# SCH_arduino_2021-11-24.net
KiCad netlist of a schematic drawn in EasyEDA
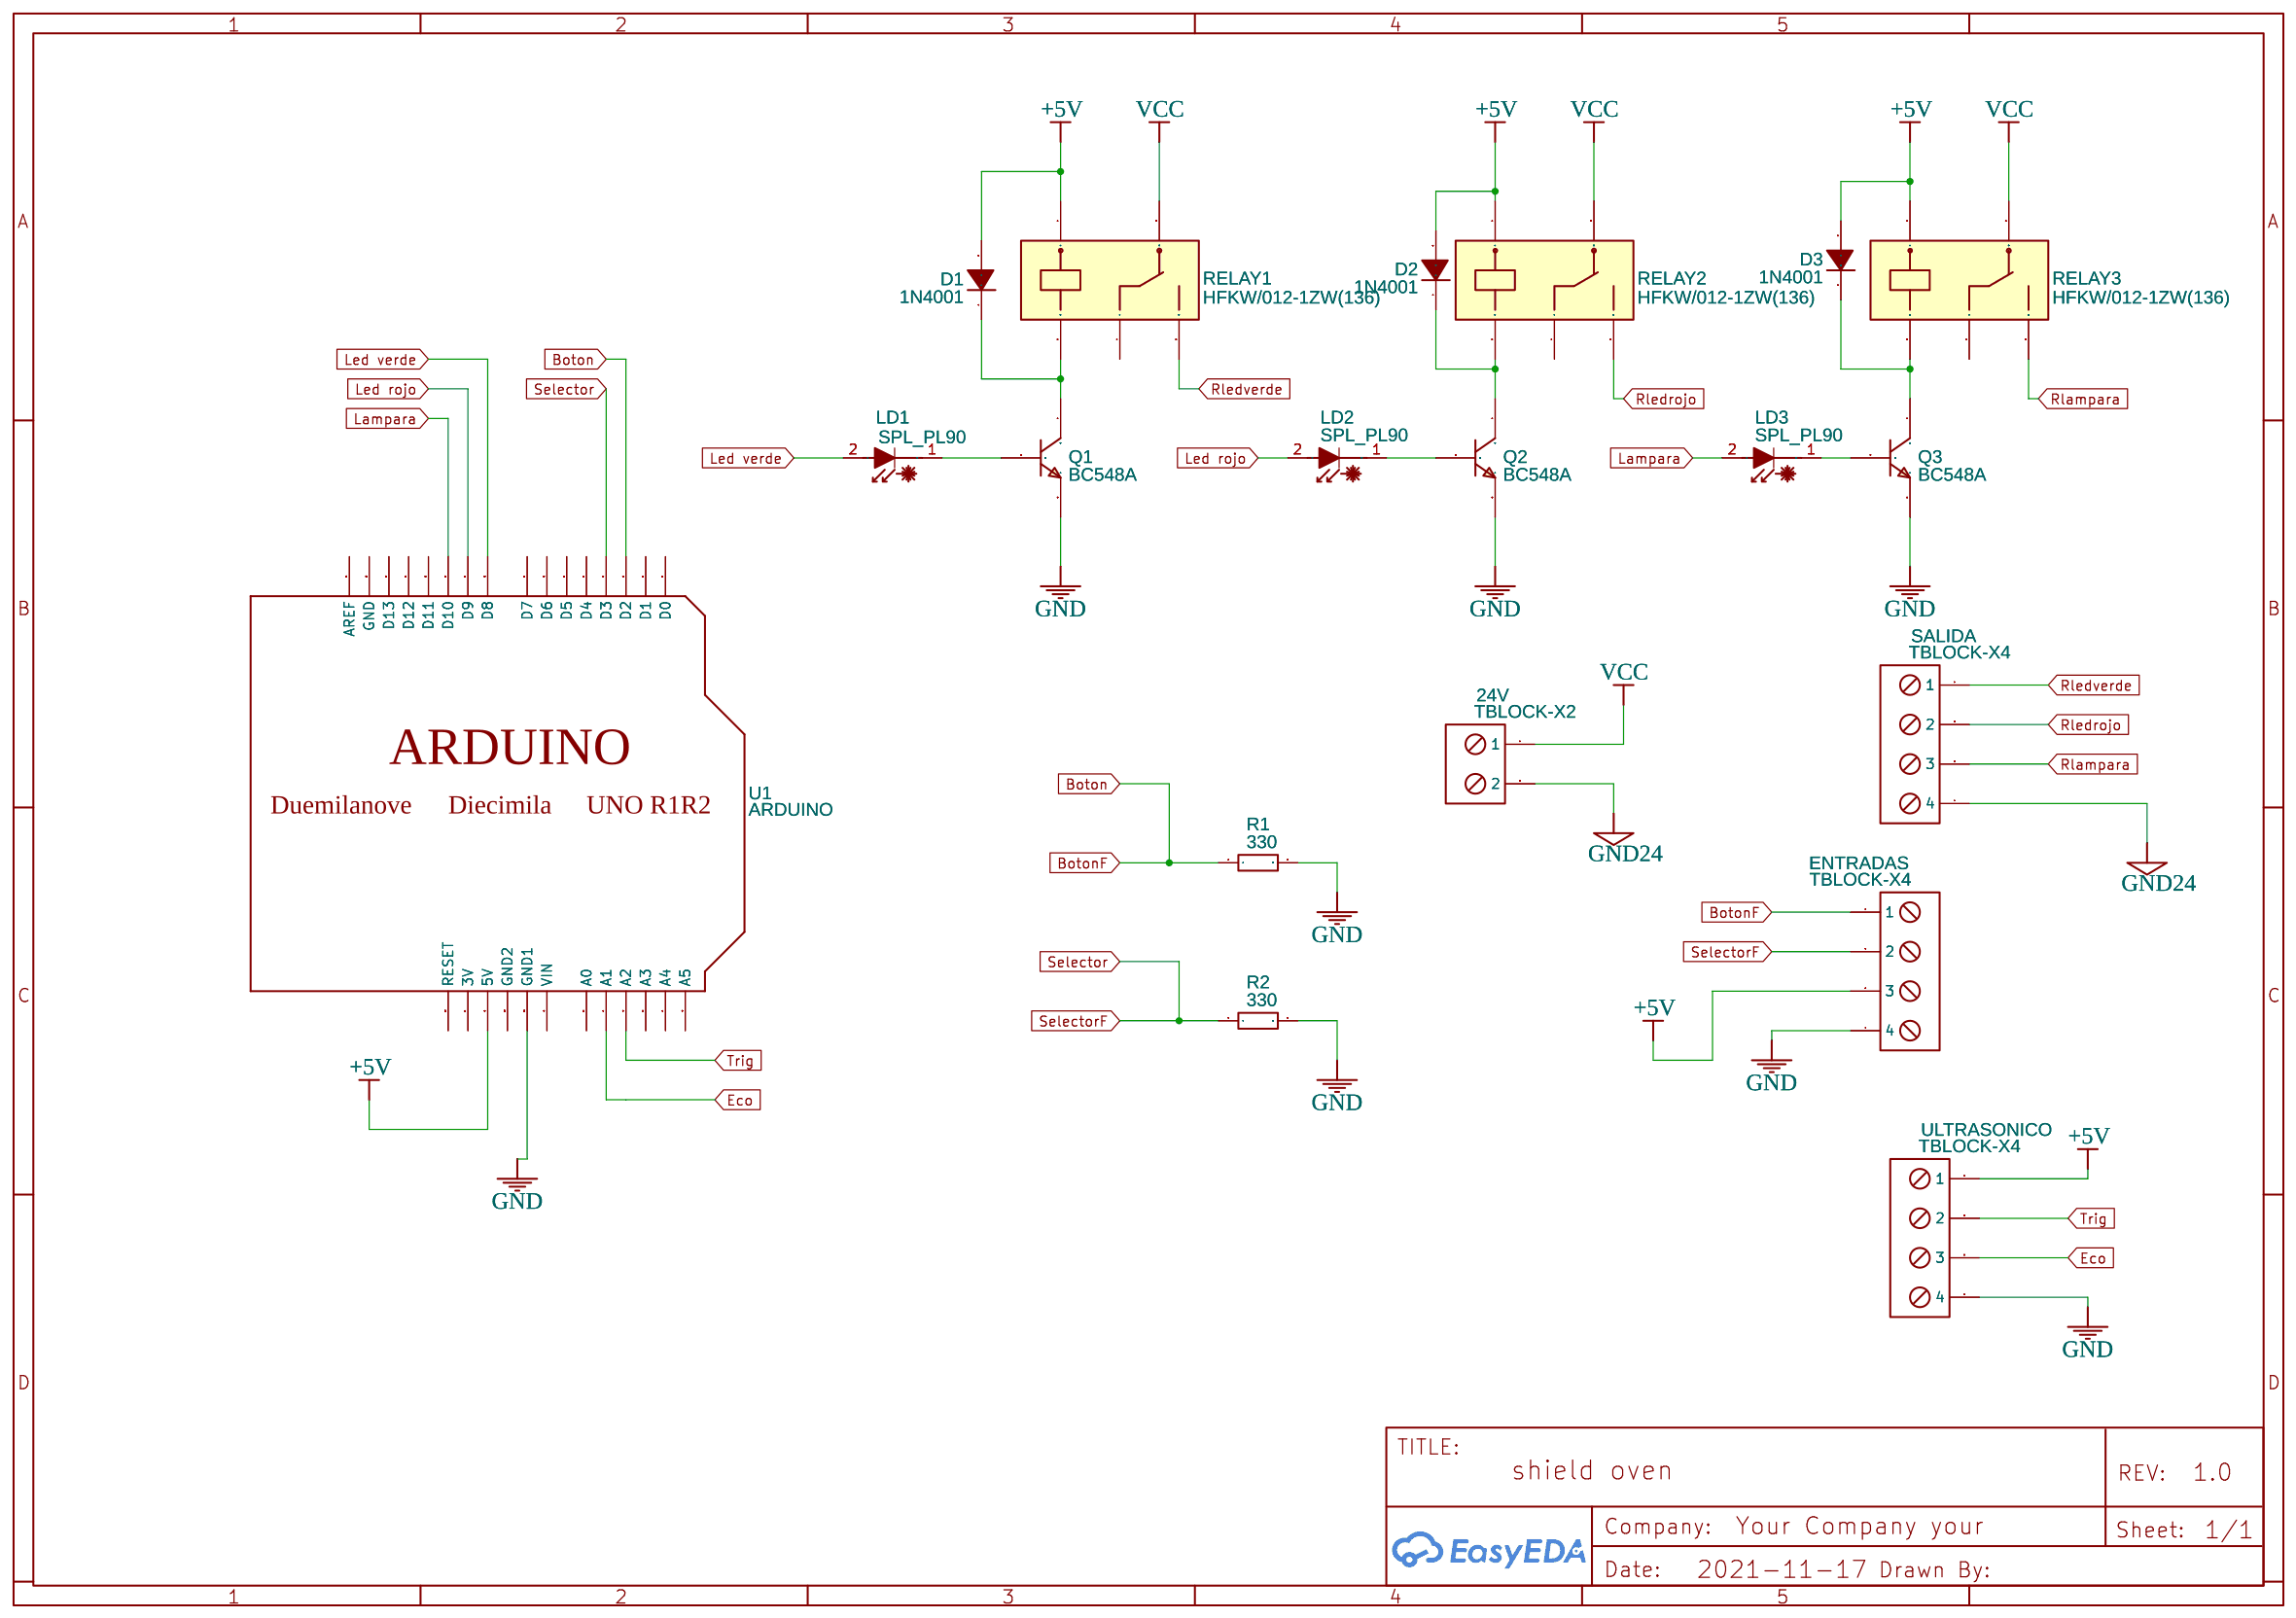
[diagram p0: schematic sheet]

(export (version "E")
  (design (tool "Eeschema 10.0.6"))
  (components
    (comp (ref "24V") (value "TBLOCK-X2") (libsource (lib "") (part "TBLOCK-X2")))
    (comp (ref "D1")
      (value "1N4001")
      (fields (field (name "BOM_Supplier Part") "C82804"))
      (libsource (lib "") (part "1N4001"))
    )
    (comp (ref "D2")
      (value "1N4001")
      (fields (field (name "BOM_Supplier Part") "C82804"))
      (libsource (lib "") (part "1N4001"))
    )
    (comp (ref "D3")
      (value "1N4001")
      (fields (field (name "BOM_Supplier Part") "C82804"))
      (libsource (lib "") (part "1N4001"))
    )
    (comp (ref "ENTRADAS") (value "TBLOCK-X4") (libsource (lib "") (part "TBLOCK-X4_2")))
    (comp (ref "LD1") (value "SPL_PL90") (libsource (lib "") (part "SPL_PL90")))
    (comp (ref "LD2") (value "SPL_PL90") (libsource (lib "") (part "SPL_PL90")))
    (comp (ref "LD3") (value "SPL_PL90") (libsource (lib "") (part "SPL_PL90")))
    (comp (ref "Q1") (value "BC548A") (libsource (lib "") (part "BC548A")))
    (comp (ref "Q2") (value "BC548A") (libsource (lib "") (part "BC548A")))
    (comp (ref "Q3") (value "BC548A") (libsource (lib "") (part "BC548A")))
    (comp (ref "R1")
      (value "330")
      (fields (field (name "BOM_Supplier Part") "C10322"))
      (libsource (lib "") (part "330Ω (331) ±5%"))
    )
    (comp (ref "R2")
      (value "330")
      (fields (field (name "BOM_Supplier Part") "C10322"))
      (libsource (lib "") (part "330Ω (331) ±5%"))
    )
    (comp (ref "RELAY1") (value "HFKW/012-1ZW(136)") (libsource (lib "") (part "HFKW/012-1ZW(136)")))
    (comp (ref "RELAY2") (value "HFKW/012-1ZW(136)") (libsource (lib "") (part "HFKW/012-1ZW(136)")))
    (comp (ref "RELAY3") (value "HFKW/012-1ZW(136)") (libsource (lib "") (part "HFKW/012-1ZW(136)")))
    (comp (ref "SALIDA") (value "TBLOCK-X4") (libsource (lib "") (part "TBLOCK-X4")))
    (comp (ref "U1") (value "ARDUINO") (libsource (lib "") (part "ARDUINO")))
    (comp (ref "ULTRASONICO") (value "TBLOCK-X4") (libsource (lib "") (part "TBLOCK-X4_1")))
  )
  (nets
    (net (code "1") (name "+5V") (class "Default")
      (node (ref "D1") (pin "2") (pinfunction "A_2") (pintype "unspecified"))
      (node (ref "D2") (pin "2") (pinfunction "A_2") (pintype "unspecified"))
      (node (ref "D3") (pin "2") (pinfunction "A_2") (pintype "unspecified"))
      (node (ref "ENTRADAS") (pin "3") (pinfunction "3_3") (pintype "unspecified"))
      (node (ref "RELAY1") (pin "1") (pinfunction "1_1") (pintype "input"))
      (node (ref "RELAY2") (pin "1") (pinfunction "1_1") (pintype "input"))
      (node (ref "RELAY3") (pin "1") (pinfunction "1_1") (pintype "input"))
      (node (ref "U1") (pin "5V") (pinfunction "5V_5V") (pintype "passive"))
      (node (ref "ULTRASONICO") (pin "1") (pinfunction "1_1") (pintype "unspecified"))
    )
    (net (code "2") (name "Boton") (class "Default")
      (node (ref "ENTRADAS") (pin "1") (pinfunction "1_1") (pintype "unspecified"))
      (node (ref "R1") (pin "1") (pinfunction "1_1") (pintype "unspecified"))
      (node (ref "U1") (pin "D2") (pinfunction "D2_D2") (pintype "unspecified"))
    )
    (net (code "3") (name "Eco") (class "Default")
      (node (ref "U1") (pin "A1") (pinfunction "A1_A1") (pintype "unspecified"))
      (node (ref "ULTRASONICO") (pin "3") (pinfunction "3_3") (pintype "unspecified"))
    )
    (net (code "4") (name "GND") (class "Default")
      (node (ref "ENTRADAS") (pin "4") (pinfunction "4_4") (pintype "unspecified"))
      (node (ref "Q1") (pin "3") (pinfunction "E_3") (pintype "unspecified"))
      (node (ref "Q2") (pin "3") (pinfunction "E_3") (pintype "unspecified"))
      (node (ref "Q3") (pin "3") (pinfunction "E_3") (pintype "unspecified"))
      (node (ref "R1") (pin "2") (pinfunction "2_2") (pintype "unspecified"))
      (node (ref "R2") (pin "2") (pinfunction "2_2") (pintype "unspecified"))
      (node (ref "U1") (pin "GND1") (pinfunction "GND1_GND1") (pintype "passive"))
      (node (ref "ULTRASONICO") (pin "4") (pinfunction "4_4") (pintype "unspecified"))
    )
    (net (code "5") (name "GND24") (class "Default")
      (node (ref "24V") (pin "2") (pinfunction "2_2") (pintype "unspecified"))
      (node (ref "SALIDA") (pin "4") (pinfunction "4_4") (pintype "unspecified"))
    )
    (net (code "6") (name "Lampara") (class "Default")
      (node (ref "LD3") (pin "2") (pinfunction "A_2") (pintype "unspecified"))
      (node (ref "U1") (pin "D10") (pinfunction "D10_D10") (pintype "unspecified"))
    )
    (net (code "7") (name "Led rojo") (class "Default")
      (node (ref "LD2") (pin "2") (pinfunction "A_2") (pintype "unspecified"))
      (node (ref "U1") (pin "D9") (pinfunction "D9_D9") (pintype "unspecified"))
    )
    (net (code "8") (name "Led verde") (class "Default")
      (node (ref "LD1") (pin "2") (pinfunction "A_2") (pintype "unspecified"))
      (node (ref "U1") (pin "D8") (pinfunction "D8_D8") (pintype "unspecified"))
    )
    (net (code "9") (name "Net-(D1-K)") (class "Default")
      (node (ref "D1") (pin "1") (pinfunction "K_1") (pintype "unspecified"))
      (node (ref "Q1") (pin "1") (pinfunction "C_1") (pintype "unspecified"))
      (node (ref "RELAY1") (pin "2") (pinfunction "2_2") (pintype "input"))
    )
    (net (code "10") (name "Net-(D2-K)") (class "Default")
      (node (ref "D2") (pin "1") (pinfunction "K_1") (pintype "unspecified"))
      (node (ref "Q2") (pin "1") (pinfunction "C_1") (pintype "unspecified"))
      (node (ref "RELAY2") (pin "2") (pinfunction "2_2") (pintype "input"))
    )
    (net (code "11") (name "Net-(D3-K)") (class "Default")
      (node (ref "D3") (pin "1") (pinfunction "K_1") (pintype "unspecified"))
      (node (ref "Q3") (pin "1") (pinfunction "C_1") (pintype "unspecified"))
      (node (ref "RELAY3") (pin "2") (pinfunction "2_2") (pintype "input"))
    )
    (net (code "12") (name "Net-(LD1-C)") (class "Default")
      (node (ref "LD1") (pin "1") (pinfunction "C_1") (pintype "unspecified"))
      (node (ref "Q1") (pin "2") (pinfunction "B_2") (pintype "unspecified"))
    )
    (net (code "13") (name "Net-(LD2-C)") (class "Default")
      (node (ref "LD2") (pin "1") (pinfunction "C_1") (pintype "unspecified"))
      (node (ref "Q2") (pin "2") (pinfunction "B_2") (pintype "unspecified"))
    )
    (net (code "14") (name "Net-(LD3-C)") (class "Default")
      (node (ref "LD3") (pin "1") (pinfunction "C_1") (pintype "unspecified"))
      (node (ref "Q3") (pin "2") (pinfunction "B_2") (pintype "unspecified"))
    )
    (net (code "15") (name "Rlampara") (class "Default")
      (node (ref "RELAY3") (pin "5") (pinfunction "5_5") (pintype "input"))
      (node (ref "SALIDA") (pin "3") (pinfunction "3_3") (pintype "unspecified"))
    )
    (net (code "16") (name "Rledrojo") (class "Default")
      (node (ref "RELAY2") (pin "5") (pinfunction "5_5") (pintype "input"))
      (node (ref "SALIDA") (pin "2") (pinfunction "2_2") (pintype "unspecified"))
    )
    (net (code "17") (name "Rledverde") (class "Default")
      (node (ref "RELAY1") (pin "5") (pinfunction "5_5") (pintype "input"))
      (node (ref "SALIDA") (pin "1") (pinfunction "1_1") (pintype "unspecified"))
    )
    (net (code "18") (name "Selector") (class "Default")
      (node (ref "ENTRADAS") (pin "2") (pinfunction "2_2") (pintype "unspecified"))
      (node (ref "R2") (pin "1") (pinfunction "1_1") (pintype "unspecified"))
      (node (ref "U1") (pin "D3") (pinfunction "D3_D3") (pintype "unspecified"))
    )
    (net (code "19") (name "Trig") (class "Default")
      (node (ref "U1") (pin "A2") (pinfunction "A2_A2") (pintype "unspecified"))
      (node (ref "ULTRASONICO") (pin "2") (pinfunction "2_2") (pintype "unspecified"))
    )
    (net (code "20") (name "VCC") (class "Default")
      (node (ref "24V") (pin "1") (pinfunction "1_1") (pintype "unspecified"))
      (node (ref "RELAY1") (pin "3") (pinfunction "3_3") (pintype "input"))
      (node (ref "RELAY2") (pin "3") (pinfunction "3_3") (pintype "input"))
      (node (ref "RELAY3") (pin "3") (pinfunction "3_3") (pintype "input"))
    )
    (net (code "21") (name "unconnected-(RELAY1-Pad4)") (class "Default")
      (node (ref "RELAY1") (pin "4") (pinfunction "4_4") (pintype "input"))
    )
    (net (code "22") (name "unconnected-(RELAY2-Pad4)") (class "Default")
      (node (ref "RELAY2") (pin "4") (pinfunction "4_4") (pintype "input"))
    )
    (net (code "23") (name "unconnected-(RELAY3-Pad4)") (class "Default")
      (node (ref "RELAY3") (pin "4") (pinfunction "4_4") (pintype "input"))
    )
    (net (code "24") (name "unconnected-(U1-Pad3V)") (class "Default")
      (node (ref "U1") (pin "3V") (pinfunction "3V_3V") (pintype "passive"))
    )
    (net (code "25") (name "unconnected-(U1-PadA0)") (class "Default")
      (node (ref "U1") (pin "A0") (pinfunction "A0_A0") (pintype "unspecified"))
    )
    (net (code "26") (name "unconnected-(U1-PadA3)") (class "Default")
      (node (ref "U1") (pin "A3") (pinfunction "A3_A3") (pintype "unspecified"))
    )
    (net (code "27") (name "unconnected-(U1-PadA4)") (class "Default")
      (node (ref "U1") (pin "A4") (pinfunction "A4_A4") (pintype "unspecified"))
    )
    (net (code "28") (name "unconnected-(U1-PadA5)") (class "Default")
      (node (ref "U1") (pin "A5") (pinfunction "A5_A5") (pintype "unspecified"))
    )
    (net (code "29") (name "unconnected-(U1-PadAREF)") (class "Default")
      (node (ref "U1") (pin "AREF") (pinfunction "AREF_AREF") (pintype "unspecified"))
    )
    (net (code "30") (name "unconnected-(U1-PadD0)") (class "Default")
      (node (ref "U1") (pin "D0") (pinfunction "D0_D0") (pintype "unspecified"))
    )
    (net (code "31") (name "unconnected-(U1-PadD1)") (class "Default")
      (node (ref "U1") (pin "D1") (pinfunction "D1_D1") (pintype "unspecified"))
    )
    (net (code "32") (name "unconnected-(U1-PadD4)") (class "Default")
      (node (ref "U1") (pin "D4") (pinfunction "D4_D4") (pintype "unspecified"))
    )
    (net (code "33") (name "unconnected-(U1-PadD5)") (class "Default")
      (node (ref "U1") (pin "D5") (pinfunction "D5_D5") (pintype "unspecified"))
    )
    (net (code "34") (name "unconnected-(U1-PadD6)") (class "Default")
      (node (ref "U1") (pin "D6") (pinfunction "D6_D6") (pintype "unspecified"))
    )
    (net (code "35") (name "unconnected-(U1-PadD7)") (class "Default")
      (node (ref "U1") (pin "D7") (pinfunction "D7_D7") (pintype "unspecified"))
    )
    (net (code "36") (name "unconnected-(U1-PadD11)") (class "Default")
      (node (ref "U1") (pin "D11") (pinfunction "D11_D11") (pintype "unspecified"))
    )
    (net (code "37") (name "unconnected-(U1-PadD12)") (class "Default")
      (node (ref "U1") (pin "D12") (pinfunction "D12_D12") (pintype "unspecified"))
    )
    (net (code "38") (name "unconnected-(U1-PadD13)") (class "Default")
      (node (ref "U1") (pin "D13") (pinfunction "D13_D13") (pintype "unspecified"))
    )
    (net (code "39") (name "unconnected-(U1-PadGND)") (class "Default")
      (node (ref "U1") (pin "GND") (pinfunction "GND_GND") (pintype "passive"))
    )
    (net (code "40") (name "unconnected-(U1-PadGND2)") (class "Default")
      (node (ref "U1") (pin "GND2") (pinfunction "GND2_GND2") (pintype "passive"))
    )
    (net (code "41") (name "unconnected-(U1-PadRESET)") (class "Default")
      (node (ref "U1") (pin "RESET") (pinfunction "RESET_RESET") (pintype "unspecified"))
    )
    (net (code "42") (name "unconnected-(U1-PadVIN)") (class "Default")
      (node (ref "U1") (pin "VIN") (pinfunction "VIN_VIN") (pintype "passive"))
    )
  )
)
